# PX4IOARv1_2.net
KiCad netlist of a schematic drawn in EAGLE
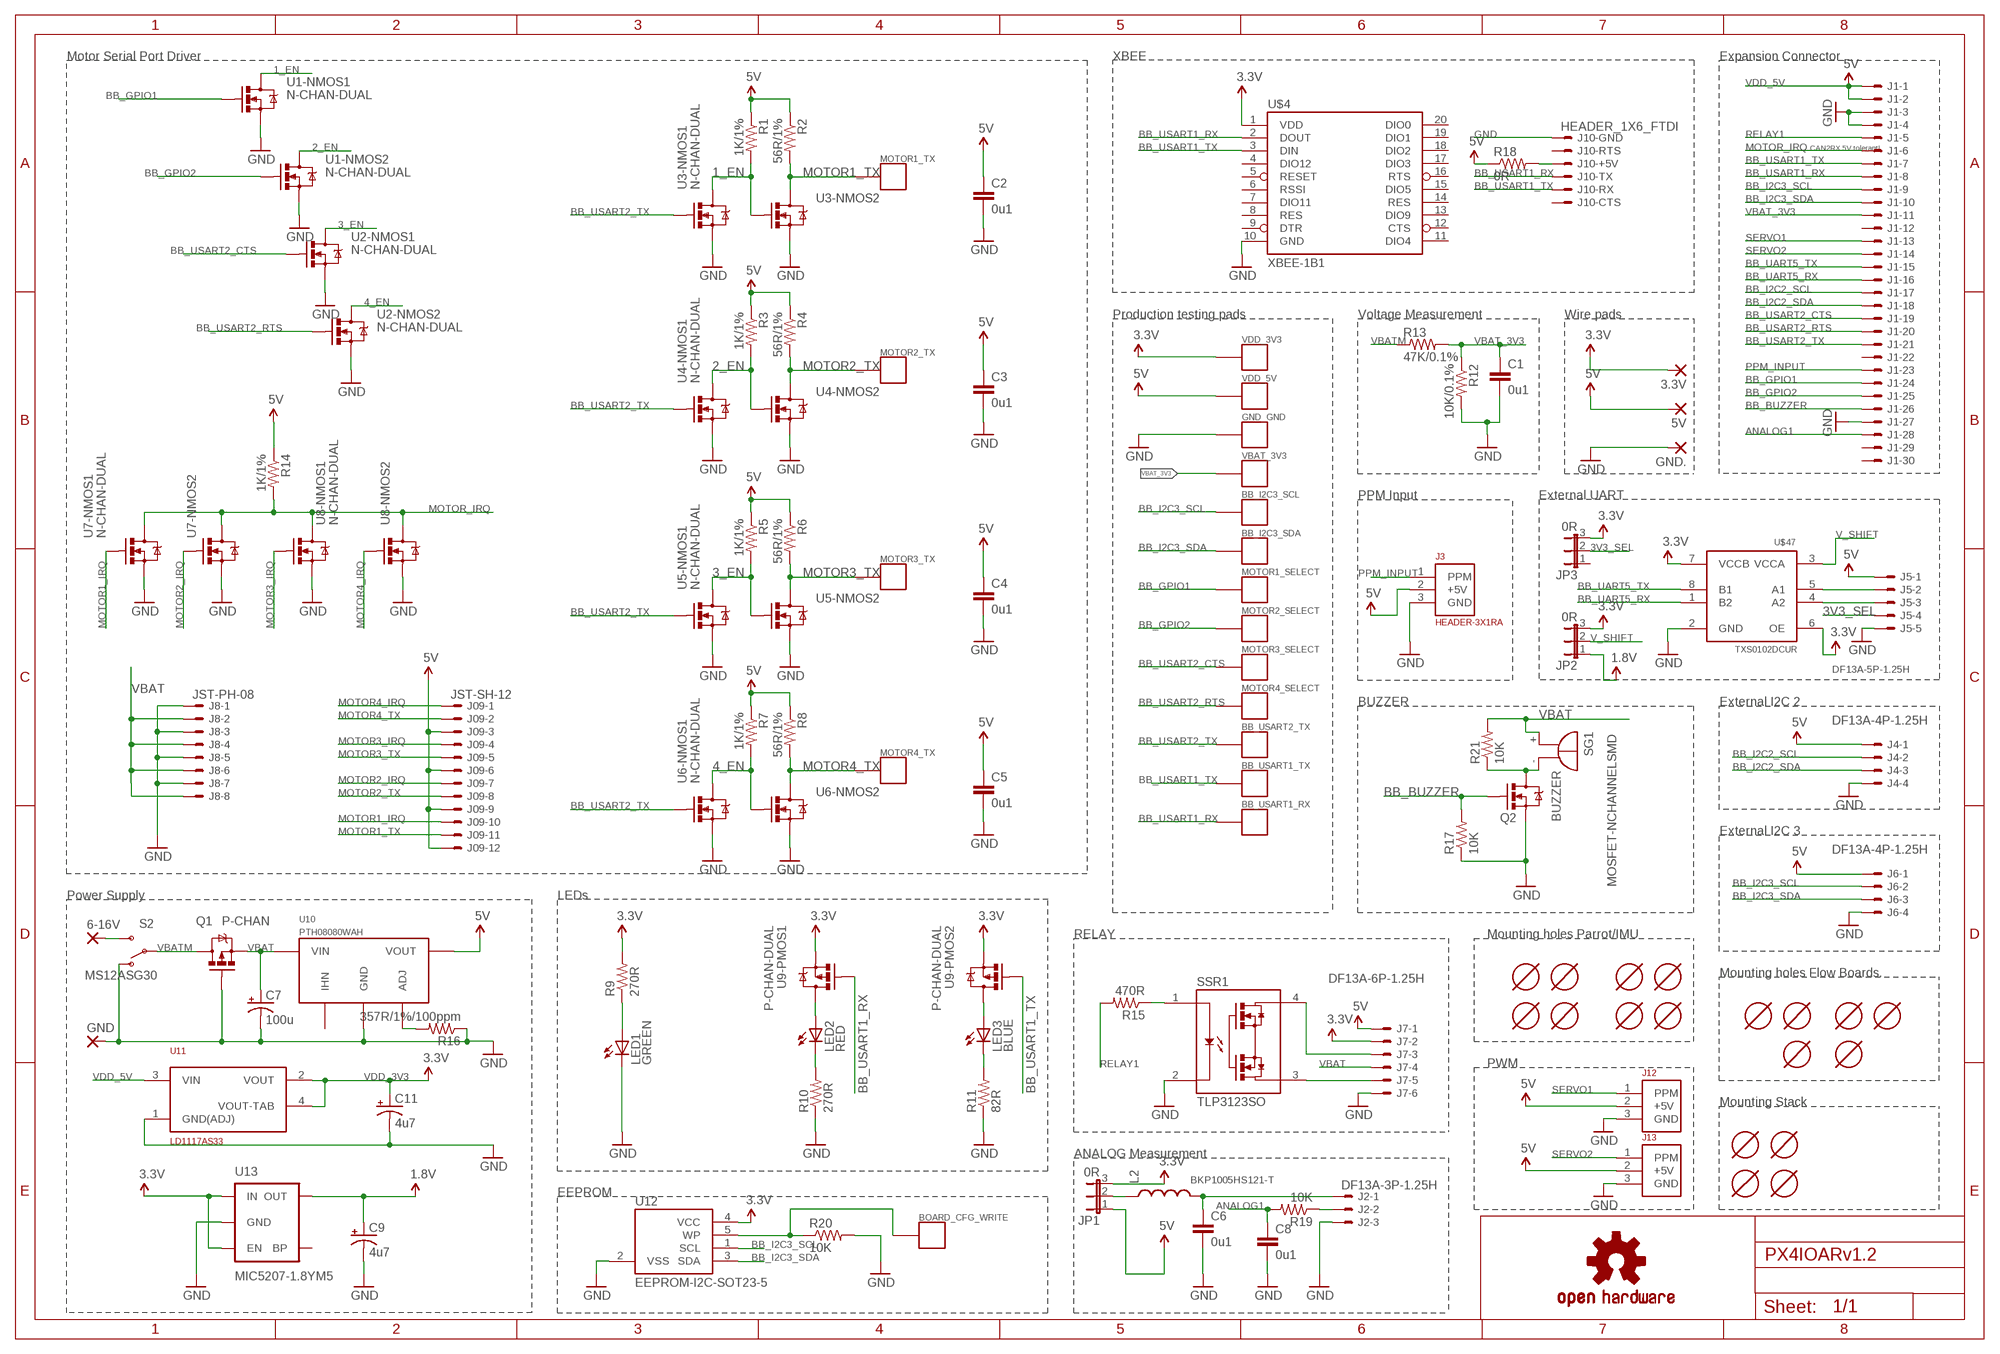
[diagram p0: schematic, sheet 1]

(export (version "E")
  (design (tool "Eeschema 10.0.6"))
  (components
    (comp (ref "3.3V")
      (value "WIREPADSMD3,5-2")
      (footprint "eagle-import:3,5-2")
      (libsource (lib "eagle-import") (part "WIREPADSMD3,5-2"))
    )
    (comp (ref "5V")
      (value "WIREPADSMD3,5-2")
      (footprint "eagle-import:3,5-2")
      (libsource (lib "eagle-import") (part "WIREPADSMD3,5-2"))
    )
    (comp (ref "6-16V")
      (value "WIREPADTH-2.0MM")
      (footprint "eagle-import:WIREPAD-TH-2.0MM")
      (libsource (lib "eagle-import") (part "WIREPADTH-2.0MM"))
    )
    (comp (ref "BB_I2C3_SCL")
      (value "PAD.05")
      (footprint "eagle-import:PAD.05X.05")
      (libsource (lib "eagle-import") (part "PAD.05"))
    )
    (comp (ref "BB_I2C3_SDA")
      (value "PAD.05")
      (footprint "eagle-import:PAD.05X.05")
      (libsource (lib "eagle-import") (part "PAD.05"))
    )
    (comp (ref "BB_USART1_RX")
      (value "PAD.05")
      (footprint "eagle-import:PAD.05X.05")
      (libsource (lib "eagle-import") (part "PAD.05"))
    )
    (comp (ref "BB_USART1_TX")
      (value "PAD.05")
      (footprint "eagle-import:PAD.05X.05")
      (libsource (lib "eagle-import") (part "PAD.05"))
    )
    (comp (ref "BB_USART2_TX")
      (value "PAD.05")
      (footprint "eagle-import:PAD.05X.05")
      (libsource (lib "eagle-import") (part "PAD.05"))
    )
    (comp (ref "BOARD_CFG_WRITE")
      (value "PAD.05")
      (footprint "eagle-import:PAD.05X.05")
      (libsource (lib "eagle-import") (part "PAD.05"))
    )
    (comp (ref "C1")
      (value "0u1")
      (footprint "eagle-import:0402-CAP")
      (fields (field (name "PARTNO") "CC0402ZRY5V7BB104"))
      (libsource (lib "eagle-import") (part "CAP0402-CAP"))
    )
    (comp (ref "C2")
      (value "0u1")
      (footprint "eagle-import:0402-CAP")
      (fields (field (name "PARTNO") "CC0402ZRY5V7BB104"))
      (libsource (lib "eagle-import") (part "CAP0402-CAP"))
    )
    (comp (ref "C3")
      (value "0u1")
      (footprint "eagle-import:0402-CAP")
      (fields (field (name "PARTNO") "CC0402ZRY5V7BB104"))
      (libsource (lib "eagle-import") (part "CAP0402-CAP"))
    )
    (comp (ref "C4")
      (value "0u1")
      (footprint "eagle-import:0402-CAP")
      (fields (field (name "PARTNO") "CC0402ZRY5V7BB104"))
      (libsource (lib "eagle-import") (part "CAP0402-CAP"))
    )
    (comp (ref "C5")
      (value "0u1")
      (footprint "eagle-import:0402-CAP")
      (fields (field (name "PARTNO") "CC0402ZRY5V7BB104"))
      (libsource (lib "eagle-import") (part "CAP0402-CAP"))
    )
    (comp (ref "C6")
      (value "0u1")
      (footprint "eagle-import:0402-CAP")
      (fields (field (name "PARTNO") "CC0402ZRY5V7BB104"))
      (libsource (lib "eagle-import") (part "CAP0402-CAP"))
    )
    (comp (ref "C7")
      (value "100u")
      (footprint "eagle-import:EIA7343")
      (fields (field (name "PARTNO") "T491X107K025ZT"))
      (libsource (lib "eagle-import") (part "CAP_POL7343"))
    )
    (comp (ref "C8")
      (value "0u1")
      (footprint "eagle-import:0402-CAP")
      (fields (field (name "PARTNO") "CC0402ZRY5V7BB104"))
      (libsource (lib "eagle-import") (part "CAP0402-CAP"))
    )
    (comp (ref "C9")
      (value "4u7")
      (footprint "eagle-import:EIA3216")
      (fields (field (name "PARTNO") "T491A475K010AT"))
      (libsource (lib "eagle-import") (part "CAP_POL1206"))
    )
    (comp (ref "C11")
      (value "4u7")
      (footprint "eagle-import:EIA3216")
      (fields (field (name "PARTNO") "T491A475K010AT"))
      (libsource (lib "eagle-import") (part "CAP_POL1206"))
    )
    (comp (ref "GND")
      (value "WIREPADTH-2.0MM")
      (footprint "eagle-import:WIREPAD-TH-2.0MM")
      (libsource (lib "eagle-import") (part "WIREPADTH-2.0MM"))
    )
    (comp (ref "GND.")
      (value "WIREPADSMD3,5-2")
      (footprint "eagle-import:3,5-2")
      (libsource (lib "eagle-import") (part "WIREPADSMD3,5-2"))
    )
    (comp (ref "GND_GND")
      (value "PAD.05")
      (footprint "eagle-import:PAD.05X.05")
      (libsource (lib "eagle-import") (part "PAD.05"))
    )
    (comp (ref "J1")
      (value "HEADER_2X15-REV")
      (footprint "eagle-import:HEADER_2MM_2X15_REVERSE")
      (fields (field (name "PARTNO") "951230-2520-AR-PR") (field (name "BOM") "INCLUDE"))
      (libsource (lib "eagle-import") (part "HEADER_2X15-REV"))
    )
    (comp (ref "J2")
      (value "DF13A-3P-1.25H")
      (footprint "eagle-import:DF13A-3P-1.25H")
      (fields (field (name "PARTNO") "DF13A-3P-1.25H(20)"))
      (libsource (lib "eagle-import") (part "DF13-3P-1.25?H"))
    )
    (comp (ref "J3")
      (value "HEADER-3X1RA")
      (footprint "eagle-import:3X1RA")
      (libsource (lib "eagle-import") (part "HEADER-3X1RA"))
    )
    (comp (ref "J4")
      (value "DF13A-4P-1.25H")
      (footprint "eagle-import:DF13A-4P-1.25H")
      (fields (field (name "PARTNO") "DF13A-4P-1.25H(20)"))
      (libsource (lib "eagle-import") (part "DF13-4P-1.25?H"))
    )
    (comp (ref "J5")
      (value "DF13A-5P-1.25H")
      (footprint "eagle-import:DF13A-5P-1.25H")
      (fields (field (name "PARTNO") "DF13A-5P-1.25H(20)"))
      (libsource (lib "eagle-import") (part "DF13-5P-1.25?H"))
    )
    (comp (ref "J6")
      (value "DF13A-4P-1.25H")
      (footprint "eagle-import:DF13A-4P-1.25H")
      (fields (field (name "PARTNO") "DF13A-4P-1.25H(20)"))
      (libsource (lib "eagle-import") (part "DF13-4P-1.25?H"))
    )
    (comp (ref "J7")
      (value "DF13A-6P-1.25H")
      (footprint "eagle-import:DF13A-6P-1.25H")
      (fields (field (name "PARTNO") "DF13A-6P-1.25H(20)"))
      (libsource (lib "eagle-import") (part "DF13-6P-1.25?H"))
    )
    (comp (ref "J8")
      (value "JST-PH-08")
      (footprint "eagle-import:B8B-PH-K-S")
      (fields (field (name "PARTNO") "B8B-PH-K-S(LF)(SN)"))
      (libsource (lib "eagle-import") (part "JST-PH-08"))
    )
    (comp (ref "J09")
      (value "JST-SH-12")
      (footprint "eagle-import:SM12B-SRSS-TB")
      (fields (field (name "PARTNO") "SM12B-SRSS-TB(LF)(SN)"))
      (libsource (lib "eagle-import") (part "JST-SH-12"))
    )
    (comp (ref "J10")
      (value "HEADER_1X6_FTDI")
      (footprint "eagle-import:HEADER_1X06-FTDI")
      (fields (field (name "BOM") "EXCLUDE"))
      (libsource (lib "eagle-import") (part "HEADER_1X6_FTDI"))
    )
    (comp (ref "J12")
      (value "HEADER-3X1SMD-BOARDEDGE")
      (footprint "eagle-import:HEADER_3X01_SMD_H_BOARD_EDGE")
      (libsource (lib "eagle-import") (part "HEADER-3X1SMD-BOARDEDGE"))
    )
    (comp (ref "J13")
      (value "HEADER-3X1SMD-BOARDEDGE")
      (footprint "eagle-import:HEADER_3X01_SMD_H_BOARD_EDGE")
      (libsource (lib "eagle-import") (part "HEADER-3X1SMD-BOARDEDGE"))
    )
    (comp (ref "JP1")
      (value "0R")
      (footprint "eagle-import:SJ_3_0603_PASTE1&2")
      (fields (field (name "PARTNO") "RMCF0402ZT0R00"))
      (libsource (lib "eagle-import") (part "JUMPER-30603"))
    )
    (comp (ref "JP2")
      (value "0R")
      (footprint "eagle-import:SJ_3_0603_PASTE1&2")
      (fields (field (name "PARTNO") "RMCF0402ZT0R00"))
      (libsource (lib "eagle-import") (part "JUMPER-30603"))
    )
    (comp (ref "JP3")
      (value "0R")
      (footprint "eagle-import:SJ_3_0603_PASTE1&2")
      (fields (field (name "PARTNO") "RMCF0402ZT0R00"))
      (libsource (lib "eagle-import") (part "JUMPER-30603"))
    )
    (comp (ref "L2")
      (value "BKP1005HS121-T")
      (footprint "eagle-import:0402-IND")
      (libsource (lib "eagle-import") (part "INDUCTOR0402"))
    )
    (comp (ref "LED1")
      (value "GREEN")
      (footprint "eagle-import:LED-0603")
      (fields (field (name "PARTNO") "LNJ337W83RA"))
      (libsource (lib "eagle-import") (part "LED0603"))
    )
    (comp (ref "LED2")
      (value "RED")
      (footprint "eagle-import:LED-0603")
      (fields (field (name "PARTNO") "LNJ237W82RA"))
      (libsource (lib "eagle-import") (part "LED0603"))
    )
    (comp (ref "LED3")
      (value "BLUE")
      (footprint "eagle-import:LED-0603")
      (fields (field (name "PARTNO") "LNJ937W8CRA"))
      (libsource (lib "eagle-import") (part "LED0603"))
    )
    (comp (ref "MOTOR1_SELECT")
      (value "PAD.05")
      (footprint "eagle-import:PAD.05X.05")
      (libsource (lib "eagle-import") (part "PAD.05"))
    )
    (comp (ref "MOTOR1_TX")
      (value "PAD.05")
      (footprint "eagle-import:PAD.05X.05")
      (libsource (lib "eagle-import") (part "PAD.05"))
    )
    (comp (ref "MOTOR2_SELECT")
      (value "PAD.05")
      (footprint "eagle-import:PAD.05X.05")
      (libsource (lib "eagle-import") (part "PAD.05"))
    )
    (comp (ref "MOTOR2_TX")
      (value "PAD.05")
      (footprint "eagle-import:PAD.05X.05")
      (libsource (lib "eagle-import") (part "PAD.05"))
    )
    (comp (ref "MOTOR3_SELECT")
      (value "PAD.05")
      (footprint "eagle-import:PAD.05X.05")
      (libsource (lib "eagle-import") (part "PAD.05"))
    )
    (comp (ref "MOTOR3_TX")
      (value "PAD.05")
      (footprint "eagle-import:PAD.05X.05")
      (libsource (lib "eagle-import") (part "PAD.05"))
    )
    (comp (ref "MOTOR4_SELECT")
      (value "PAD.05")
      (footprint "eagle-import:PAD.05X.05")
      (libsource (lib "eagle-import") (part "PAD.05"))
    )
    (comp (ref "MOTOR4_TX")
      (value "PAD.05")
      (footprint "eagle-import:PAD.05X.05")
      (libsource (lib "eagle-import") (part "PAD.05"))
    )
    (comp (ref "Q1")
      (value "P-CHAN")
      (footprint "eagle-import:DPAK")
      (fields (field (name "PARTNO") "IRFR5505TRPBF"))
      (libsource (lib "eagle-import") (part "MOSFET-PCHANNEL-DPAK"))
    )
    (comp (ref "Q2")
      (value "MOSFET-NCHANNELSMD")
      (footprint "eagle-import:SOT23-3")
      (fields (field (name "PARTNO") "ZXMS6004FFTA"))
      (libsource (lib "eagle-import") (part "MOSFET-NCHANNELSMD"))
    )
    (comp (ref "R1")
      (value "1K/1%")
      (footprint "eagle-import:0402-RES")
      (fields (field (name "PARTNO") "RMCF0402FT1K00"))
      (libsource (lib "eagle-import") (part "RESISTOR0402-RES"))
    )
    (comp (ref "R2")
      (value "56R/1%")
      (footprint "eagle-import:0402-RES")
      (fields (field (name "PARTNO") "ERJ-2RKF56R0X"))
      (libsource (lib "eagle-import") (part "RESISTOR0402-RES"))
    )
    (comp (ref "R3")
      (value "1K/1%")
      (footprint "eagle-import:0402-RES")
      (fields (field (name "PARTNO") "RMCF0402FT1K00"))
      (libsource (lib "eagle-import") (part "RESISTOR0402-RES"))
    )
    (comp (ref "R4")
      (value "56R/1%")
      (footprint "eagle-import:0402-RES")
      (fields (field (name "PARTNO") "ERJ-2RKF56R0X"))
      (libsource (lib "eagle-import") (part "RESISTOR0402-RES"))
    )
    (comp (ref "R5")
      (value "1K/1%")
      (footprint "eagle-import:0402-RES")
      (fields (field (name "PARTNO") "RMCF0402FT1K00"))
      (libsource (lib "eagle-import") (part "RESISTOR0402-RES"))
    )
    (comp (ref "R6")
      (value "56R/1%")
      (footprint "eagle-import:0402-RES")
      (fields (field (name "PARTNO") "ERJ-2RKF56R0X"))
      (libsource (lib "eagle-import") (part "RESISTOR0402-RES"))
    )
    (comp (ref "R7")
      (value "1K/1%")
      (footprint "eagle-import:0402-RES")
      (fields (field (name "PARTNO") "RMCF0402FT1K00"))
      (libsource (lib "eagle-import") (part "RESISTOR0402-RES"))
    )
    (comp (ref "R8")
      (value "56R/1%")
      (footprint "eagle-import:0402-RES")
      (fields (field (name "PARTNO") "ERJ-2RKF56R0X"))
      (libsource (lib "eagle-import") (part "RESISTOR0402-RES"))
    )
    (comp (ref "R9")
      (value "270R")
      (footprint "eagle-import:0402-RES")
      (fields (field (name "PARTNO") "RC0402JR-07270RL"))
      (libsource (lib "eagle-import") (part "RESISTOR0402-RES"))
    )
    (comp (ref "R10")
      (value "270R")
      (footprint "eagle-import:0402-RES")
      (fields (field (name "PARTNO") "RC0402JR-07270RL"))
      (libsource (lib "eagle-import") (part "RESISTOR0402-RES"))
    )
    (comp (ref "R11")
      (value "82R")
      (footprint "eagle-import:0402-RES")
      (fields (field (name "PARTNO") "RC0402JR-0782RL"))
      (libsource (lib "eagle-import") (part "RESISTOR0402-RES"))
    )
    (comp (ref "R12")
      (value "10K/0.1%")
      (footprint "eagle-import:0402-RES")
      (fields (field (name "PARTNO") "ERA-2AEB103X"))
      (libsource (lib "eagle-import") (part "RESISTOR0402-RES"))
    )
    (comp (ref "R13")
      (value "47K/0.1%")
      (footprint "eagle-import:0402-RES")
      (fields (field (name "PARTNO") "ERA-2AEB473X"))
      (libsource (lib "eagle-import") (part "RESISTOR0402-RES"))
    )
    (comp (ref "R14")
      (value "1K/1%")
      (footprint "eagle-import:0402-RES")
      (fields (field (name "PARTNO") "RMCF0402FT1K00"))
      (libsource (lib "eagle-import") (part "RESISTOR0402-RES"))
    )
    (comp (ref "R15")
      (value "470R")
      (footprint "eagle-import:0402-RES")
      (fields (field (name "PARTNO") "RC0402JR-07470RL"))
      (libsource (lib "eagle-import") (part "RESISTOR0402-RES"))
    )
    (comp (ref "R16")
      (value "357R/1%/100ppm")
      (footprint "eagle-import:0402-RES")
      (fields (field (name "PARTNO") "ERJ-2RKF3570X"))
      (libsource (lib "eagle-import") (part "RESISTOR0402-RES"))
    )
    (comp (ref "R17")
      (value "10K")
      (footprint "eagle-import:0402-RES")
      (fields (field (name "PARTNO") "RMCF0402FT10K0"))
      (libsource (lib "eagle-import") (part "RESISTOR0402-RES"))
    )
    (comp (ref "R18")
      (value "0R")
      (footprint "eagle-import:0402-RES")
      (fields (field (name "PARTNO") "RMCF0402ZT0R00"))
      (libsource (lib "eagle-import") (part "RESISTOR0402-RES"))
    )
    (comp (ref "R19")
      (value "10K")
      (footprint "eagle-import:0402-RES")
      (fields (field (name "PARTNO") "RMCF0402FT10K0"))
      (libsource (lib "eagle-import") (part "RESISTOR0402-RES"))
    )
    (comp (ref "R20")
      (value "10K")
      (footprint "eagle-import:0402-RES")
      (fields (field (name "PARTNO") "RMCF0402FT10K0"))
      (libsource (lib "eagle-import") (part "RESISTOR0402-RES"))
    )
    (comp (ref "R21")
      (value "10K")
      (footprint "eagle-import:0402-RES")
      (fields (field (name "PARTNO") "RMCF0402FT10K0"))
      (libsource (lib "eagle-import") (part "RESISTOR0402-RES"))
    )
    (comp (ref "S2")
      (value "MS12ASG30")
      (footprint "eagle-import:SWITCH-SPDT-TH-HORZ")
      (libsource (lib "eagle-import") (part "SWITCH-SPSTPTH-HORZ"))
    )
    (comp (ref "SG1")
      (value "BUZZER")
      (footprint "eagle-import:F_TMB")
      (fields (field (name "PARTNO") "PKM13EPYH4000-A0"))
      (libsource (lib "eagle-import") (part "BUZZER"))
    )
    (comp (ref "SSR1")
      (value "TLP3123SO")
      (footprint "eagle-import:SOP4-2.54")
      (fields (field (name "PARTNO") "TLP3123(F)"))
      (libsource (lib "eagle-import") (part "TLP3123SO"))
    )
    (comp (ref "U$1")
      (value "MOUNT-HOLE2.6MM")
      (footprint "eagle-import:MOUNT-HOLE2.6")
      (libsource (lib "eagle-import") (part "MOUNT-HOLE2.6MM"))
    )
    (comp (ref "U$4")
      (value "XBEE-1B1")
      (footprint "eagle-import:XBEE-1")
      (fields (field (name "PARTNO") "NPPN101BFCN-RC"))
      (libsource (lib "eagle-import") (part "XBEE-1B1"))
    )
    (comp (ref "U$6")
      (value "MOUNT-HOLE3.1MM")
      (footprint "eagle-import:MOUNT-HOLE3.1")
      (libsource (lib "eagle-import") (part "MOUNT-HOLE3.1MM"))
    )
    (comp (ref "U$7")
      (value "MOUNT-HOLE3.1MM")
      (footprint "eagle-import:MOUNT-HOLE3.1")
      (libsource (lib "eagle-import") (part "MOUNT-HOLE3.1MM"))
    )
    (comp (ref "U$8")
      (value "MOUNT-HOLE2.6MM")
      (footprint "eagle-import:MOUNT-HOLE2.6")
      (libsource (lib "eagle-import") (part "MOUNT-HOLE2.6MM"))
    )
    (comp (ref "U$9")
      (value "OSHW-LOGOM")
      (footprint "eagle-import:OSHW-LOGO-M")
      (libsource (lib "eagle-import") (part "OSHW-LOGOM"))
    )
    (comp (ref "U$17")
      (value "MOUNT-HOLE3.1MM")
      (footprint "eagle-import:MOUNT-HOLE3.1")
      (libsource (lib "eagle-import") (part "MOUNT-HOLE3.1MM"))
    )
    (comp (ref "U$19")
      (value "MOUNT-HOLE3.1MM")
      (footprint "eagle-import:MOUNT-HOLE3.1")
      (libsource (lib "eagle-import") (part "MOUNT-HOLE3.1MM"))
    )
    (comp (ref "U$21")
      (value "MOUNT-HOLE3.1MM")
      (footprint "eagle-import:MOUNT-HOLE3.1")
      (libsource (lib "eagle-import") (part "MOUNT-HOLE3.1MM"))
    )
    (comp (ref "U$29")
      (value "MOUNT-HOLE3.1MM")
      (footprint "eagle-import:MOUNT-HOLE3.1")
      (libsource (lib "eagle-import") (part "MOUNT-HOLE3.1MM"))
    )
    (comp (ref "U$30")
      (value "MOUNT-HOLE3.1MM")
      (footprint "eagle-import:MOUNT-HOLE3.1")
      (libsource (lib "eagle-import") (part "MOUNT-HOLE3.1MM"))
    )
    (comp (ref "U$31")
      (value "MOUNT-HOLE2.6MM")
      (footprint "eagle-import:MOUNT-HOLE2.6")
      (libsource (lib "eagle-import") (part "MOUNT-HOLE2.6MM"))
    )
    (comp (ref "U$32")
      (value "MOUNT-HOLE2.6MM")
      (footprint "eagle-import:MOUNT-HOLE2.6")
      (libsource (lib "eagle-import") (part "MOUNT-HOLE2.6MM"))
    )
    (comp (ref "U$33")
      (value "MOUNT-HOLE2.6MM")
      (footprint "eagle-import:MOUNT-HOLE2.6")
      (libsource (lib "eagle-import") (part "MOUNT-HOLE2.6MM"))
    )
    (comp (ref "U$34")
      (value "MOUNT-HOLE2.6MM")
      (footprint "eagle-import:MOUNT-HOLE2.6")
      (libsource (lib "eagle-import") (part "MOUNT-HOLE2.6MM"))
    )
    (comp (ref "U$40")
      (value "MOUNT-HOLE3.1MM")
      (footprint "eagle-import:MOUNT-HOLE3.1")
      (libsource (lib "eagle-import") (part "MOUNT-HOLE3.1MM"))
    )
    (comp (ref "U$43")
      (value "MOUNT-HOLE3.1MM")
      (footprint "eagle-import:MOUNT-HOLE3.1")
      (libsource (lib "eagle-import") (part "MOUNT-HOLE3.1MM"))
    )
    (comp (ref "U$44")
      (value "MOUNT-HOLE3.1MM")
      (footprint "eagle-import:MOUNT-HOLE3.1")
      (libsource (lib "eagle-import") (part "MOUNT-HOLE3.1MM"))
    )
    (comp (ref "U$45")
      (value "MOUNT-HOLE3.1MM")
      (footprint "eagle-import:MOUNT-HOLE3.1")
      (libsource (lib "eagle-import") (part "MOUNT-HOLE3.1MM"))
    )
    (comp (ref "U$46")
      (value "MOUNT-HOLE3.1MM")
      (footprint "eagle-import:MOUNT-HOLE3.1")
      (libsource (lib "eagle-import") (part "MOUNT-HOLE3.1MM"))
    )
    (comp (ref "U$47")
      (value "TXS0102DCUR")
      (footprint "eagle-import:TI-DCU")
      (libsource (lib "eagle-import") (part "TXS0102DCUR"))
    )
    (comp (ref "U1")
      (value "N-CHAN-DUAL")
      (footprint "eagle-import:SOT363_PHILIPS")
      (fields (field (name "PARTNO") "2N7002PS,115"))
      (libsource (lib "eagle-import") (part "MOSFET-DUAL-NCHANNEL-SOT363"))
    )
    (comp (ref "U2")
      (value "N-CHAN-DUAL")
      (footprint "eagle-import:SOT363_PHILIPS")
      (fields (field (name "PARTNO") "2N7002PS,115"))
      (libsource (lib "eagle-import") (part "MOSFET-DUAL-NCHANNEL-SOT363"))
    )
    (comp (ref "U3")
      (value "N-CHAN-DUAL")
      (footprint "eagle-import:SOT363_PHILIPS")
      (fields (field (name "PARTNO") "2N7002PS,115"))
      (libsource (lib "eagle-import") (part "MOSFET-DUAL-NCHANNEL-SOT363"))
    )
    (comp (ref "U4")
      (value "N-CHAN-DUAL")
      (footprint "eagle-import:SOT363_PHILIPS")
      (fields (field (name "PARTNO") "2N7002PS,115"))
      (libsource (lib "eagle-import") (part "MOSFET-DUAL-NCHANNEL-SOT363"))
    )
    (comp (ref "U5")
      (value "N-CHAN-DUAL")
      (footprint "eagle-import:SOT363_PHILIPS")
      (fields (field (name "PARTNO") "2N7002PS,115"))
      (libsource (lib "eagle-import") (part "MOSFET-DUAL-NCHANNEL-SOT363"))
    )
    (comp (ref "U6")
      (value "N-CHAN-DUAL")
      (footprint "eagle-import:SOT363_PHILIPS")
      (fields (field (name "PARTNO") "2N7002PS,115"))
      (libsource (lib "eagle-import") (part "MOSFET-DUAL-NCHANNEL-SOT363"))
    )
    (comp (ref "U7")
      (value "N-CHAN-DUAL")
      (footprint "eagle-import:SOT363_PHILIPS")
      (fields (field (name "PARTNO") "2N7002PS,115"))
      (libsource (lib "eagle-import") (part "MOSFET-DUAL-NCHANNEL-SOT363"))
    )
    (comp (ref "U8")
      (value "N-CHAN-DUAL")
      (footprint "eagle-import:SOT363_PHILIPS")
      (fields (field (name "PARTNO") "2N7002PS,115"))
      (libsource (lib "eagle-import") (part "MOSFET-DUAL-NCHANNEL-SOT363"))
    )
    (comp (ref "U9")
      (value "P-CHAN-DUAL")
      (footprint "eagle-import:SOT363_PHILIPS")
      (fields (field (name "PARTNO") "BSS84DW-7-F"))
      (libsource (lib "eagle-import") (part "MOSFET-DUAL-PCHANNEL-SOT363"))
    )
    (comp (ref "U10")
      (value "PTH08080WAH")
      (footprint "eagle-import:PTH08080W_TH")
      (libsource (lib "eagle-import") (part "PTH08080WAH"))
    )
    (comp (ref "U11")
      (value "LD1117AS33")
      (footprint "eagle-import:SOT-223")
      (libsource (lib "eagle-import") (part "LD1117AS33"))
    )
    (comp (ref "U12")
      (value "EEPROM-I2C-SOT23-5")
      (footprint "eagle-import:SOT23-5")
      (fields (field (name "PARTNO") "24LC01BT-I/OT"))
      (libsource (lib "eagle-import") (part "EEPROM-I2C-?SOT23-5"))
    )
    (comp (ref "U13")
      (value "MIC5207-1.8YM5")
      (footprint "eagle-import:SOT23-5")
      (libsource (lib "eagle-import") (part "V_REG_LDOSMD"))
    )
    (comp (ref "VBAT_3V3")
      (value "PAD.05")
      (footprint "eagle-import:PAD.05X.05")
      (libsource (lib "eagle-import") (part "PAD.05"))
    )
    (comp (ref "VDD_3V3")
      (value "PAD.05")
      (footprint "eagle-import:PAD.05X.05")
      (libsource (lib "eagle-import") (part "PAD.05"))
    )
    (comp (ref "VDD_5V")
      (value "PAD.05")
      (footprint "eagle-import:PAD.05X.05")
      (libsource (lib "eagle-import") (part "PAD.05"))
    )
  )
  (nets
    (net (code "1") (name "/1_EN") (class "Default")
      (node (ref "R1") (pin "2") (pinfunction "2_2") (pintype "passive"))
      (node (ref "U1") (pin "6") (pinfunction "D_6") (pintype "passive"))
      (node (ref "U3") (pin "5") (pinfunction "G_5") (pintype "passive"))
      (node (ref "U3") (pin "6") (pinfunction "D_6") (pintype "passive"))
    )
    (net (code "2") (name "/2_EN") (class "Default")
      (node (ref "R3") (pin "2") (pinfunction "2_2") (pintype "passive"))
      (node (ref "U1") (pin "3") (pinfunction "D_3") (pintype "passive"))
      (node (ref "U4") (pin "5") (pinfunction "G_5") (pintype "passive"))
      (node (ref "U4") (pin "6") (pinfunction "D_6") (pintype "passive"))
    )
    (net (code "3") (name "/3V3_SEL") (class "Default")
      (node (ref "J5") (pin "4") (pinfunction "S_4") (pintype "passive"))
      (node (ref "JP3") (pin "2") (pinfunction "2_2") (pintype "passive"))
    )
    (net (code "4") (name "/3_EN") (class "Default")
      (node (ref "R5") (pin "2") (pinfunction "2_2") (pintype "passive"))
      (node (ref "U2") (pin "6") (pinfunction "D_6") (pintype "passive"))
      (node (ref "U5") (pin "5") (pinfunction "G_5") (pintype "passive"))
      (node (ref "U5") (pin "6") (pinfunction "D_6") (pintype "passive"))
    )
    (net (code "5") (name "/4_EN") (class "Default")
      (node (ref "R7") (pin "2") (pinfunction "2_2") (pintype "passive"))
      (node (ref "U2") (pin "3") (pinfunction "D_3") (pintype "passive"))
      (node (ref "U6") (pin "5") (pinfunction "G_5") (pintype "passive"))
      (node (ref "U6") (pin "6") (pinfunction "D_6") (pintype "passive"))
    )
    (net (code "6") (name "/ANALOG1") (class "Default")
      (node (ref "C8") (pin "1") (pinfunction "1_1") (pintype "passive"))
      (node (ref "J1") (pin "28") (pinfunction "S_28") (pintype "passive"))
      (node (ref "R19") (pin "2") (pinfunction "2_2") (pintype "passive"))
    )
    (net (code "7") (name "/BB_BUZZER") (class "Default")
      (node (ref "J1") (pin "26") (pinfunction "S_26") (pintype "passive"))
      (node (ref "Q2") (pin "1") (pinfunction "G_1") (pintype "passive"))
      (node (ref "R17") (pin "2") (pinfunction "2_2") (pintype "passive"))
    )
    (net (code "8") (name "/BB_GPIO1") (class "Default")
      (node (ref "J1") (pin "24") (pinfunction "S_24") (pintype "passive"))
      (node (ref "MOTOR1_SELECT") (pin "P$1") (pinfunction "P$1_P$1") (pintype "passive"))
      (node (ref "U1") (pin "2") (pinfunction "G_2") (pintype "passive"))
    )
    (net (code "9") (name "/BB_GPIO2") (class "Default")
      (node (ref "J1") (pin "25") (pinfunction "S_25") (pintype "passive"))
      (node (ref "MOTOR2_SELECT") (pin "P$1") (pinfunction "P$1_P$1") (pintype "passive"))
      (node (ref "U1") (pin "5") (pinfunction "G_5") (pintype "passive"))
    )
    (net (code "10") (name "/BB_I2C2_SCL") (class "Default")
      (node (ref "J1") (pin "17") (pinfunction "S_17") (pintype "passive"))
      (node (ref "J4") (pin "2") (pinfunction "S_2") (pintype "passive"))
    )
    (net (code "11") (name "/BB_I2C2_SDA") (class "Default")
      (node (ref "J1") (pin "18") (pinfunction "S_18") (pintype "passive"))
      (node (ref "J4") (pin "3") (pinfunction "S_3") (pintype "passive"))
    )
    (net (code "12") (name "/BB_I2C3_SCL") (class "Default")
      (node (ref "BB_I2C3_SCL") (pin "P$1") (pinfunction "P$1_P$1") (pintype "passive"))
      (node (ref "J1") (pin "9") (pinfunction "S_9") (pintype "passive"))
      (node (ref "J6") (pin "2") (pinfunction "S_2") (pintype "passive"))
      (node (ref "U12") (pin "1") (pinfunction "SCL_1") (pintype "bidirectional"))
    )
    (net (code "13") (name "/BB_I2C3_SDA") (class "Default")
      (node (ref "BB_I2C3_SDA") (pin "P$1") (pinfunction "P$1_P$1") (pintype "passive"))
      (node (ref "J1") (pin "10") (pinfunction "S_10") (pintype "passive"))
      (node (ref "J6") (pin "3") (pinfunction "S_3") (pintype "passive"))
      (node (ref "U12") (pin "3") (pinfunction "SDA_3") (pintype "bidirectional"))
    )
    (net (code "14") (name "/BB_UART5_RX") (class "Default")
      (node (ref "J1") (pin "16") (pinfunction "S_16") (pintype "passive"))
      (node (ref "U$47") (pin "1") (pinfunction "B2_1") (pintype "bidirectional"))
    )
    (net (code "15") (name "/BB_UART5_TX") (class "Default")
      (node (ref "J1") (pin "15") (pinfunction "S_15") (pintype "passive"))
      (node (ref "U$47") (pin "8") (pinfunction "B1_8") (pintype "bidirectional"))
    )
    (net (code "16") (name "/BB_USART1_RX") (class "Default")
      (node (ref "BB_USART1_RX") (pin "P$1") (pinfunction "P$1_P$1") (pintype "passive"))
      (node (ref "J1") (pin "8") (pinfunction "S_8") (pintype "passive"))
      (node (ref "J10") (pin "RX") (pinfunction "S_RX") (pintype "passive"))
      (node (ref "U$4") (pin "2") (pinfunction "DOUT_2") (pintype "output"))
      (node (ref "U9") (pin "5") (pinfunction "G_5") (pintype "passive"))
    )
    (net (code "17") (name "/BB_USART1_TX") (class "Default")
      (node (ref "BB_USART1_TX") (pin "P$1") (pinfunction "P$1_P$1") (pintype "passive"))
      (node (ref "J1") (pin "7") (pinfunction "S_7") (pintype "passive"))
      (node (ref "J10") (pin "TX") (pinfunction "S_TX") (pintype "passive"))
      (node (ref "U$4") (pin "3") (pinfunction "DIN_3") (pintype "input"))
      (node (ref "U9") (pin "2") (pinfunction "G_2") (pintype "passive"))
    )
    (net (code "18") (name "/BB_USART2_CTS") (class "Default")
      (node (ref "J1") (pin "19") (pinfunction "S_19") (pintype "passive"))
      (node (ref "MOTOR3_SELECT") (pin "P$1") (pinfunction "P$1_P$1") (pintype "passive"))
      (node (ref "U2") (pin "2") (pinfunction "G_2") (pintype "passive"))
    )
    (net (code "19") (name "/BB_USART2_RTS") (class "Default")
      (node (ref "J1") (pin "20") (pinfunction "S_20") (pintype "passive"))
      (node (ref "MOTOR4_SELECT") (pin "P$1") (pinfunction "P$1_P$1") (pintype "passive"))
      (node (ref "U2") (pin "5") (pinfunction "G_5") (pintype "passive"))
    )
    (net (code "20") (name "/BB_USART2_TX") (class "Default")
      (node (ref "BB_USART2_TX") (pin "P$1") (pinfunction "P$1_P$1") (pintype "passive"))
      (node (ref "J1") (pin "21") (pinfunction "S_21") (pintype "passive"))
      (node (ref "U3") (pin "2") (pinfunction "G_2") (pintype "passive"))
      (node (ref "U4") (pin "2") (pinfunction "G_2") (pintype "passive"))
      (node (ref "U5") (pin "2") (pinfunction "G_2") (pintype "passive"))
      (node (ref "U6") (pin "2") (pinfunction "G_2") (pintype "passive"))
    )
    (net (code "21") (name "/MOTOR1_IRQ") (class "Default")
      (node (ref "J09") (pin "10") (pinfunction "S_10") (pintype "passive"))
      (node (ref "U7") (pin "2") (pinfunction "G_2") (pintype "passive"))
    )
    (net (code "22") (name "/MOTOR1_TX") (class "Default")
      (node (ref "J09") (pin "11") (pinfunction "S_11") (pintype "passive"))
      (node (ref "MOTOR1_TX") (pin "P$1") (pinfunction "P$1_P$1") (pintype "passive"))
      (node (ref "R2") (pin "2") (pinfunction "2_2") (pintype "passive"))
      (node (ref "U3") (pin "3") (pinfunction "D_3") (pintype "passive"))
    )
    (net (code "23") (name "/MOTOR2_IRQ") (class "Default")
      (node (ref "J09") (pin "7") (pinfunction "S_7") (pintype "passive"))
      (node (ref "U7") (pin "5") (pinfunction "G_5") (pintype "passive"))
    )
    (net (code "24") (name "/MOTOR2_TX") (class "Default")
      (node (ref "J09") (pin "8") (pinfunction "S_8") (pintype "passive"))
      (node (ref "MOTOR2_TX") (pin "P$1") (pinfunction "P$1_P$1") (pintype "passive"))
      (node (ref "R4") (pin "2") (pinfunction "2_2") (pintype "passive"))
      (node (ref "U4") (pin "3") (pinfunction "D_3") (pintype "passive"))
    )
    (net (code "25") (name "/MOTOR3_IRQ") (class "Default")
      (node (ref "J09") (pin "4") (pinfunction "S_4") (pintype "passive"))
      (node (ref "U8") (pin "2") (pinfunction "G_2") (pintype "passive"))
    )
    (net (code "26") (name "/MOTOR3_TX") (class "Default")
      (node (ref "J09") (pin "5") (pinfunction "S_5") (pintype "passive"))
      (node (ref "MOTOR3_TX") (pin "P$1") (pinfunction "P$1_P$1") (pintype "passive"))
      (node (ref "R6") (pin "2") (pinfunction "2_2") (pintype "passive"))
      (node (ref "U5") (pin "3") (pinfunction "D_3") (pintype "passive"))
    )
    (net (code "27") (name "/MOTOR4_IRQ") (class "Default")
      (node (ref "J09") (pin "1") (pinfunction "S_1") (pintype "passive"))
      (node (ref "U8") (pin "5") (pinfunction "G_5") (pintype "passive"))
    )
    (net (code "28") (name "/MOTOR4_TX") (class "Default")
      (node (ref "J09") (pin "2") (pinfunction "S_2") (pintype "passive"))
      (node (ref "MOTOR4_TX") (pin "P$1") (pinfunction "P$1_P$1") (pintype "passive"))
      (node (ref "R8") (pin "2") (pinfunction "2_2") (pintype "passive"))
      (node (ref "U6") (pin "3") (pinfunction "D_3") (pintype "passive"))
    )
    (net (code "29") (name "/MOTOR_IRQ") (class "Default")
      (node (ref "J1") (pin "6") (pinfunction "S_6") (pintype "passive"))
      (node (ref "R14") (pin "2") (pinfunction "2_2") (pintype "passive"))
      (node (ref "U7") (pin "3") (pinfunction "D_3") (pintype "passive"))
      (node (ref "U7") (pin "6") (pinfunction "D_6") (pintype "passive"))
      (node (ref "U8") (pin "3") (pinfunction "D_3") (pintype "passive"))
      (node (ref "U8") (pin "6") (pinfunction "D_6") (pintype "passive"))
    )
    (net (code "30") (name "/PPM_INPUT") (class "Default")
      (node (ref "J1") (pin "23") (pinfunction "S_23") (pintype "passive"))
      (node (ref "J3") (pin "1") (pinfunction "PPM_1") (pintype "bidirectional"))
    )
    (net (code "31") (name "/RELAY1") (class "Default")
      (node (ref "J1") (pin "5") (pinfunction "S_5") (pintype "passive"))
      (node (ref "R15") (pin "2") (pinfunction "2_2") (pintype "passive"))
    )
    (net (code "32") (name "/SERVO1") (class "Default")
      (node (ref "J1") (pin "13") (pinfunction "S_13") (pintype "passive"))
      (node (ref "J12") (pin "1") (pinfunction "PPM_1") (pintype "bidirectional"))
    )
    (net (code "33") (name "/SERVO2") (class "Default")
      (node (ref "J1") (pin "14") (pinfunction "S_14") (pintype "passive"))
      (node (ref "J13") (pin "1") (pinfunction "PPM_1") (pintype "bidirectional"))
    )
    (net (code "34") (name "/VBAT") (class "Default")
      (node (ref "C7") (pin "A") (pinfunction "+_A") (pintype "passive"))
      (node (ref "J7") (pin "4") (pinfunction "S_4") (pintype "passive"))
      (node (ref "J8") (pin "2") (pinfunction "S_2") (pintype "passive"))
      (node (ref "J8") (pin "4") (pinfunction "S_4") (pintype "passive"))
      (node (ref "J8") (pin "6") (pinfunction "S_6") (pintype "passive"))
      (node (ref "J8") (pin "8") (pinfunction "S_8") (pintype "passive"))
      (node (ref "Q1") (pin "3") (pinfunction "S_3") (pintype "passive"))
      (node (ref "R21") (pin "2") (pinfunction "2_2") (pintype "passive"))
      (node (ref "SG1") (pin "+") (pinfunction "+_+") (pintype "passive"))
      (node (ref "U10") (pin "1") (pinfunction "VIN_1") (pintype "power_in"))
    )
    (net (code "35") (name "/VBATM") (class "Default")
      (node (ref "Q1") (pin "4") (pinfunction "D_4") (pintype "passive"))
      (node (ref "R13") (pin "1") (pinfunction "1_1") (pintype "passive"))
      (node (ref "S2") (pin "2") (pinfunction "P_2") (pintype "passive"))
    )
    (net (code "36") (name "/V_SHIFT") (class "Default")
      (node (ref "JP2") (pin "2") (pinfunction "2_2") (pintype "passive"))
      (node (ref "U$47") (pin "3") (pinfunction "VCCA_3") (pintype "input"))
    )
    (net (code "37") (name "1.8V") (class "Default")
      (node (ref "C9") (pin "A") (pinfunction "+_A") (pintype "passive"))
      (node (ref "JP2") (pin "1") (pinfunction "1_1") (pintype "passive"))
      (node (ref "U13") (pin "5") (pinfunction "OUT_5") (pintype "passive"))
    )
    (net (code "38") (name "3.3V") (class "Default")
      (node (ref "3.3V") (pin "1") (pinfunction "P_1") (pintype "passive"))
      (node (ref "C11") (pin "A") (pinfunction "+_A") (pintype "passive"))
      (node (ref "J7") (pin "2") (pinfunction "S_2") (pintype "passive"))
      (node (ref "JP1") (pin "3") (pinfunction "3_3") (pintype "passive"))
      (node (ref "JP2") (pin "3") (pinfunction "3_3") (pintype "passive"))
      (node (ref "JP3") (pin "3") (pinfunction "3_3") (pintype "passive"))
      (node (ref "R9") (pin "2") (pinfunction "2_2") (pintype "passive"))
      (node (ref "U$4") (pin "1") (pinfunction "VDD_1") (pintype "power_in"))
      (node (ref "U$47") (pin "6") (pinfunction "OE_6") (pintype "input"))
      (node (ref "U$47") (pin "7") (pinfunction "VCCB_7") (pintype "input"))
      (node (ref "U11") (pin "2") (pinfunction "VOUT_2") (pintype "bidirectional"))
      (node (ref "U11") (pin "4") (pinfunction "VOUT-TAB_4") (pintype "bidirectional"))
      (node (ref "U12") (pin "4") (pinfunction "VCC_4") (pintype "power_in"))
      (node (ref "U13") (pin "1") (pinfunction "IN_1") (pintype "input"))
      (node (ref "U13") (pin "3") (pinfunction "EN_3") (pintype "input"))
      (node (ref "U9") (pin "1") (pinfunction "S_1") (pintype "passive"))
      (node (ref "U9") (pin "4") (pinfunction "S_4") (pintype "passive"))
      (node (ref "VDD_3V3") (pin "P$1") (pinfunction "P$1_P$1") (pintype "passive"))
    )
    (net (code "39") (name "5V") (class "Default")
      (node (ref "5V") (pin "1") (pinfunction "P_1") (pintype "passive"))
      (node (ref "C2") (pin "1") (pinfunction "1_1") (pintype "passive"))
      (node (ref "C3") (pin "1") (pinfunction "1_1") (pintype "passive"))
      (node (ref "C4") (pin "1") (pinfunction "1_1") (pintype "passive"))
      (node (ref "C5") (pin "1") (pinfunction "1_1") (pintype "passive"))
      (node (ref "J09") (pin "12") (pinfunction "S_12") (pintype "passive"))
      (node (ref "J09") (pin "3") (pinfunction "S_3") (pintype "passive"))
      (node (ref "J09") (pin "6") (pinfunction "S_6") (pintype "passive"))
      (node (ref "J09") (pin "9") (pinfunction "S_9") (pintype "passive"))
      (node (ref "J1") (pin "1") (pinfunction "S_1") (pintype "passive"))
      (node (ref "J1") (pin "2") (pinfunction "S_2") (pintype "passive"))
      (node (ref "J12") (pin "2") (pinfunction "+5V_2") (pintype "bidirectional"))
      (node (ref "J13") (pin "2") (pinfunction "+5V_2") (pintype "bidirectional"))
      (node (ref "J3") (pin "2") (pinfunction "+5V_2") (pintype "bidirectional"))
      (node (ref "J4") (pin "1") (pinfunction "S_1") (pintype "passive"))
      (node (ref "J5") (pin "1") (pinfunction "S_1") (pintype "passive"))
      (node (ref "J6") (pin "1") (pinfunction "S_1") (pintype "passive"))
      (node (ref "J7") (pin "1") (pinfunction "S_1") (pintype "passive"))
      (node (ref "JP1") (pin "1") (pinfunction "1_1") (pintype "passive"))
      (node (ref "R1") (pin "1") (pinfunction "1_1") (pintype "passive"))
      (node (ref "R14") (pin "1") (pinfunction "1_1") (pintype "passive"))
      (node (ref "R18") (pin "1") (pinfunction "1_1") (pintype "passive"))
      (node (ref "R2") (pin "1") (pinfunction "1_1") (pintype "passive"))
      (node (ref "R3") (pin "1") (pinfunction "1_1") (pintype "passive"))
      (node (ref "R4") (pin "1") (pinfunction "1_1") (pintype "passive"))
      (node (ref "R5") (pin "1") (pinfunction "1_1") (pintype "passive"))
      (node (ref "R6") (pin "1") (pinfunction "1_1") (pintype "passive"))
      (node (ref "R7") (pin "1") (pinfunction "1_1") (pintype "passive"))
      (node (ref "R8") (pin "1") (pinfunction "1_1") (pintype "passive"))
      (node (ref "U10") (pin "3") (pinfunction "VOUT_3") (pintype "power_in"))
      (node (ref "U11") (pin "3") (pinfunction "VIN_3") (pintype "bidirectional"))
      (node (ref "VDD_5V") (pin "P$1") (pinfunction "P$1_P$1") (pintype "passive"))
    )
    (net (code "40") (name "GND") (class "Default")
      (node (ref "C1") (pin "2") (pinfunction "2_2") (pintype "passive"))
      (node (ref "C11") (pin "C") (pinfunction "-_C") (pintype "passive"))
      (node (ref "C2") (pin "2") (pinfunction "2_2") (pintype "passive"))
      (node (ref "C3") (pin "2") (pinfunction "2_2") (pintype "passive"))
      (node (ref "C4") (pin "2") (pinfunction "2_2") (pintype "passive"))
      (node (ref "C5") (pin "2") (pinfunction "2_2") (pintype "passive"))
      (node (ref "C6") (pin "2") (pinfunction "2_2") (pintype "passive"))
      (node (ref "C7") (pin "C") (pinfunction "-_C") (pintype "passive"))
      (node (ref "C8") (pin "2") (pinfunction "2_2") (pintype "passive"))
      (node (ref "C9") (pin "C") (pinfunction "-_C") (pintype "passive"))
      (node (ref "GND") (pin "1") (pinfunction "P_1") (pintype "passive"))
      (node (ref "GND.") (pin "1") (pinfunction "P_1") (pintype "passive"))
      (node (ref "GND_GND") (pin "P$1") (pinfunction "P$1_P$1") (pintype "passive"))
      (node (ref "J1") (pin "27") (pinfunction "S_27") (pintype "passive"))
      (node (ref "J1") (pin "3") (pinfunction "S_3") (pintype "passive"))
      (node (ref "J1") (pin "4") (pinfunction "S_4") (pintype "passive"))
      (node (ref "J10") (pin "GND") (pinfunction "S_GND") (pintype "passive"))
      (node (ref "J12") (pin "3") (pinfunction "GND_3") (pintype "bidirectional"))
      (node (ref "J13") (pin "3") (pinfunction "GND_3") (pintype "bidirectional"))
      (node (ref "J2") (pin "3") (pinfunction "S_3") (pintype "passive"))
      (node (ref "J3") (pin "3") (pinfunction "GND_3") (pintype "bidirectional"))
      (node (ref "J4") (pin "4") (pinfunction "S_4") (pintype "passive"))
      (node (ref "J5") (pin "5") (pinfunction "S_5") (pintype "passive"))
      (node (ref "J6") (pin "4") (pinfunction "S_4") (pintype "passive"))
      (node (ref "J7") (pin "6") (pinfunction "S_6") (pintype "passive"))
      (node (ref "J8") (pin "1") (pinfunction "S_1") (pintype "passive"))
      (node (ref "J8") (pin "3") (pinfunction "S_3") (pintype "passive"))
      (node (ref "J8") (pin "5") (pinfunction "S_5") (pintype "passive"))
      (node (ref "J8") (pin "7") (pinfunction "S_7") (pintype "passive"))
      (node (ref "LED1") (pin "C") (pinfunction "C_C") (pintype "passive"))
      (node (ref "Q1") (pin "1") (pinfunction "G_1") (pintype "passive"))
      (node (ref "Q2") (pin "2") (pinfunction "S_2") (pintype "passive"))
      (node (ref "R10") (pin "1") (pinfunction "1_1") (pintype "passive"))
      (node (ref "R11") (pin "1") (pinfunction "1_1") (pintype "passive"))
      (node (ref "R12") (pin "2") (pinfunction "2_2") (pintype "passive"))
      (node (ref "R16") (pin "1") (pinfunction "1_1") (pintype "passive"))
      (node (ref "R17") (pin "1") (pinfunction "1_1") (pintype "passive"))
      (node (ref "R20") (pin "2") (pinfunction "2_2") (pintype "passive"))
      (node (ref "S2") (pin "1") (pinfunction "O_1") (pintype "passive"))
      (node (ref "SSR1") (pin "2") (pinfunction "2_2") (pintype "bidirectional"))
      (node (ref "U$4") (pin "10") (pinfunction "GND_10") (pintype "power_in"))
      (node (ref "U$47") (pin "2") (pinfunction "GND_2") (pintype "power_in"))
      (node (ref "U1") (pin "1") (pinfunction "S_1") (pintype "passive"))
      (node (ref "U1") (pin "4") (pinfunction "S_4") (pintype "passive"))
      (node (ref "U10") (pin "2") (pinfunction "GND_2") (pintype "power_in"))
      (node (ref "U11") (pin "1") (pinfunction "GND(ADJ)_1") (pintype "bidirectional"))
      (node (ref "U12") (pin "2") (pinfunction "VSS_2") (pintype "power_in"))
      (node (ref "U13") (pin "2") (pinfunction "GND_2") (pintype "input"))
      (node (ref "U2") (pin "1") (pinfunction "S_1") (pintype "passive"))
      (node (ref "U2") (pin "4") (pinfunction "S_4") (pintype "passive"))
      (node (ref "U3") (pin "1") (pinfunction "S_1") (pintype "passive"))
      (node (ref "U3") (pin "4") (pinfunction "S_4") (pintype "passive"))
      (node (ref "U4") (pin "1") (pinfunction "S_1") (pintype "passive"))
      (node (ref "U4") (pin "4") (pinfunction "S_4") (pintype "passive"))
      (node (ref "U5") (pin "1") (pinfunction "S_1") (pintype "passive"))
      (node (ref "U5") (pin "4") (pinfunction "S_4") (pintype "passive"))
      (node (ref "U6") (pin "1") (pinfunction "S_1") (pintype "passive"))
      (node (ref "U6") (pin "4") (pinfunction "S_4") (pintype "passive"))
      (node (ref "U7") (pin "1") (pinfunction "S_1") (pintype "passive"))
      (node (ref "U7") (pin "4") (pinfunction "S_4") (pintype "passive"))
      (node (ref "U8") (pin "1") (pinfunction "S_1") (pintype "passive"))
      (node (ref "U8") (pin "4") (pinfunction "S_4") (pintype "passive"))
    )
    (net (code "41") (name "Net-(6-16V-P)") (class "Default")
      (node (ref "6-16V") (pin "1") (pinfunction "P_1") (pintype "passive"))
      (node (ref "S2") (pin "3") (pinfunction "S_3") (pintype "passive"))
    )
    (net (code "42") (name "Net-(J2A-S)") (class "Default")
      (node (ref "C6") (pin "1") (pinfunction "1_1") (pintype "passive"))
      (node (ref "J2") (pin "1") (pinfunction "S_1") (pintype "passive"))
      (node (ref "L2") (pin "2") (pinfunction "2_2") (pintype "passive"))
    )
    (net (code "43") (name "Net-(J2B-S)") (class "Default")
      (node (ref "J2") (pin "2") (pinfunction "S_2") (pintype "passive"))
      (node (ref "R19") (pin "1") (pinfunction "1_1") (pintype "passive"))
    )
    (net (code "44") (name "Net-(J5B-S)") (class "Default")
      (node (ref "J5") (pin "2") (pinfunction "S_2") (pintype "passive"))
      (node (ref "U$47") (pin "5") (pinfunction "A1_5") (pintype "bidirectional"))
    )
    (net (code "45") (name "Net-(J5C-S)") (class "Default")
      (node (ref "J5") (pin "3") (pinfunction "S_3") (pintype "passive"))
      (node (ref "U$47") (pin "4") (pinfunction "A2_4") (pintype "bidirectional"))
    )
    (net (code "46") (name "Net-(J7C-S)") (class "Default")
      (node (ref "J7") (pin "3") (pinfunction "S_3") (pintype "passive"))
      (node (ref "SSR1") (pin "4") (pinfunction "4_4") (pintype "bidirectional"))
    )
    (net (code "47") (name "Net-(J7E-S)") (class "Default")
      (node (ref "J7") (pin "5") (pinfunction "S_5") (pintype "passive"))
      (node (ref "SSR1") (pin "3") (pinfunction "3_3") (pintype "bidirectional"))
    )
    (net (code "48") (name "Net-(J10A-S)") (class "Default")
      (node (ref "J10") (pin "+5V") (pinfunction "S_+5V") (pintype "passive"))
      (node (ref "R18") (pin "2") (pinfunction "2_2") (pintype "passive"))
    )
    (net (code "49") (name "Net-(JP1-Pad2)") (class "Default")
      (node (ref "JP1") (pin "2") (pinfunction "2_2") (pintype "passive"))
      (node (ref "L2") (pin "1") (pinfunction "1_1") (pintype "passive"))
    )
    (net (code "50") (name "Net-(LED1-PadA)") (class "Default")
      (node (ref "LED1") (pin "A") (pinfunction "A_A") (pintype "passive"))
      (node (ref "R9") (pin "1") (pinfunction "1_1") (pintype "passive"))
    )
    (net (code "51") (name "Net-(LED2-PadC)") (class "Default")
      (node (ref "LED2") (pin "C") (pinfunction "C_C") (pintype "passive"))
      (node (ref "R10") (pin "2") (pinfunction "2_2") (pintype "passive"))
    )
    (net (code "52") (name "Net-(LED3-PadC)") (class "Default")
      (node (ref "LED3") (pin "C") (pinfunction "C_C") (pintype "passive"))
      (node (ref "R11") (pin "2") (pinfunction "2_2") (pintype "passive"))
    )
    (net (code "53") (name "Net-(Q2-D)") (class "Default")
      (node (ref "Q2") (pin "3") (pinfunction "D_3") (pintype "passive"))
      (node (ref "R21") (pin "1") (pinfunction "1_1") (pintype "passive"))
      (node (ref "SG1") (pin "-") (pinfunction "-_-") (pintype "passive"))
    )
    (net (code "54") (name "Net-(R15-Pad1)") (class "Default")
      (node (ref "R15") (pin "1") (pinfunction "1_1") (pintype "passive"))
      (node (ref "SSR1") (pin "1") (pinfunction "1_1") (pintype "bidirectional"))
    )
    (net (code "55") (name "Net-(U9A-D)") (class "Default")
      (node (ref "LED2") (pin "A") (pinfunction "A_A") (pintype "passive"))
      (node (ref "U9") (pin "3") (pinfunction "D_3") (pintype "passive"))
    )
    (net (code "56") (name "Net-(U9B-D)") (class "Default")
      (node (ref "LED3") (pin "A") (pinfunction "A_A") (pintype "passive"))
      (node (ref "U9") (pin "6") (pinfunction "D_6") (pintype "passive"))
    )
    (net (code "57") (name "Net-(U10-ADJ)") (class "Default")
      (node (ref "R16") (pin "2") (pinfunction "2_2") (pintype "passive"))
      (node (ref "U10") (pin "4") (pinfunction "ADJ_4") (pintype "bidirectional"))
    )
    (net (code "58") (name "Net-(U12-WP)") (class "Default")
      (node (ref "BOARD_CFG_WRITE") (pin "P$1") (pinfunction "P$1_P$1") (pintype "passive"))
      (node (ref "R20") (pin "1") (pinfunction "1_1") (pintype "passive"))
      (node (ref "U12") (pin "5") (pinfunction "WP_5") (pintype "bidirectional"))
    )
    (net (code "59") (name "VBAT_3V3") (class "Default")
      (node (ref "C1") (pin "1") (pinfunction "1_1") (pintype "passive"))
      (node (ref "J1") (pin "11") (pinfunction "S_11") (pintype "passive"))
      (node (ref "R12") (pin "1") (pinfunction "1_1") (pintype "passive"))
      (node (ref "R13") (pin "2") (pinfunction "2_2") (pintype "passive"))
      (node (ref "VBAT_3V3") (pin "P$1") (pinfunction "P$1_P$1") (pintype "passive"))
    )
    (net (code "60") (name "unconnected-(J1D-S-Pad12)") (class "Default")
      (node (ref "J1") (pin "12") (pinfunction "S_12") (pintype "passive"))
    )
    (net (code "61") (name "unconnected-(J1O-S-Pad22)") (class "Default")
      (node (ref "J1") (pin "22") (pinfunction "S_22") (pintype "passive"))
    )
    (net (code "62") (name "unconnected-(J1V-S-Pad29)") (class "Default")
      (node (ref "J1") (pin "29") (pinfunction "S_29") (pintype "passive"))
    )
    (net (code "63") (name "unconnected-(J1X-S-Pad30)") (class "Default")
      (node (ref "J1") (pin "30") (pinfunction "S_30") (pintype "passive"))
    )
    (net (code "64") (name "unconnected-(J10B-S-PadCTS)") (class "Default")
      (node (ref "J10") (pin "CTS") (pinfunction "S_CTS") (pintype "passive"))
    )
    (net (code "65") (name "unconnected-(J10D-S-PadRTS)") (class "Default")
      (node (ref "J10") (pin "RTS") (pinfunction "S_RTS") (pintype "passive"))
    )
    (net (code "66") (name "unconnected-(JP3-Pad1)") (class "Default")
      (node (ref "JP3") (pin "1") (pinfunction "1_1") (pintype "passive"))
    )
    (net (code "67") (name "unconnected-(U$4-CTS-Pad12)") (class "Default")
      (node (ref "U$4") (pin "12") (pinfunction "CTS_12") (pintype "output"))
    )
    (net (code "68") (name "unconnected-(U$4-DIO0-Pad20)") (class "Default")
      (node (ref "U$4") (pin "20") (pinfunction "DIO0_20") (pintype "bidirectional"))
    )
    (net (code "69") (name "unconnected-(U$4-DIO1-Pad19)") (class "Default")
      (node (ref "U$4") (pin "19") (pinfunction "DIO1_19") (pintype "bidirectional"))
    )
    (net (code "70") (name "unconnected-(U$4-DIO2-Pad18)") (class "Default")
      (node (ref "U$4") (pin "18") (pinfunction "DIO2_18") (pintype "bidirectional"))
    )
    (net (code "71") (name "unconnected-(U$4-DIO3-Pad17)") (class "Default")
      (node (ref "U$4") (pin "17") (pinfunction "DIO3_17") (pintype "bidirectional"))
    )
    (net (code "72") (name "unconnected-(U$4-DIO4-Pad11)") (class "Default")
      (node (ref "U$4") (pin "11") (pinfunction "DIO4_11") (pintype "bidirectional"))
    )
    (net (code "73") (name "unconnected-(U$4-DIO5-Pad15)") (class "Default")
      (node (ref "U$4") (pin "15") (pinfunction "DIO5_15") (pintype "bidirectional"))
    )
    (net (code "74") (name "unconnected-(U$4-DIO9-Pad13)") (class "Default")
      (node (ref "U$4") (pin "13") (pinfunction "DIO9_13") (pintype "bidirectional"))
    )
    (net (code "75") (name "unconnected-(U$4-DIO11-Pad7)") (class "Default")
      (node (ref "U$4") (pin "7") (pinfunction "DIO11_7") (pintype "bidirectional"))
    )
    (net (code "76") (name "unconnected-(U$4-DIO12-Pad4)") (class "Default")
      (node (ref "U$4") (pin "4") (pinfunction "DIO12_4") (pintype "bidirectional"))
    )
    (net (code "77") (name "unconnected-(U$4-DTR-Pad9)") (class "Default")
      (node (ref "U$4") (pin "9") (pinfunction "DTR_9") (pintype "bidirectional"))
    )
    (net (code "78") (name "unconnected-(U$4-RES-Pad8)") (class "Default")
      (node (ref "U$4") (pin "8") (pinfunction "RES_8") (pintype "bidirectional"))
    )
    (net (code "79") (name "unconnected-(U$4-RES-Pad14)") (class "Default")
      (node (ref "U$4") (pin "14") (pinfunction "RES_14") (pintype "bidirectional"))
    )
    (net (code "80") (name "unconnected-(U$4-RESET-Pad5)") (class "Default")
      (node (ref "U$4") (pin "5") (pinfunction "RESET_5") (pintype "input"))
    )
    (net (code "81") (name "unconnected-(U$4-RSSI-Pad6)") (class "Default")
      (node (ref "U$4") (pin "6") (pinfunction "RSSI_6") (pintype "bidirectional"))
    )
    (net (code "82") (name "unconnected-(U$4-RTS-Pad16)") (class "Default")
      (node (ref "U$4") (pin "16") (pinfunction "RTS_16") (pintype "input"))
    )
    (net (code "83") (name "unconnected-(U10-IHN-Pad5)") (class "Default")
      (node (ref "U10") (pin "5") (pinfunction "IHN_5") (pintype "bidirectional"))
    )
    (net (code "84") (name "unconnected-(U13-BP-Pad4)") (class "Default")
      (node (ref "U13") (pin "4") (pinfunction "BP_4") (pintype "input"))
    )
  )
)
